# sensorboard.net
KiCad netlist of a schematic drawn in EAGLE
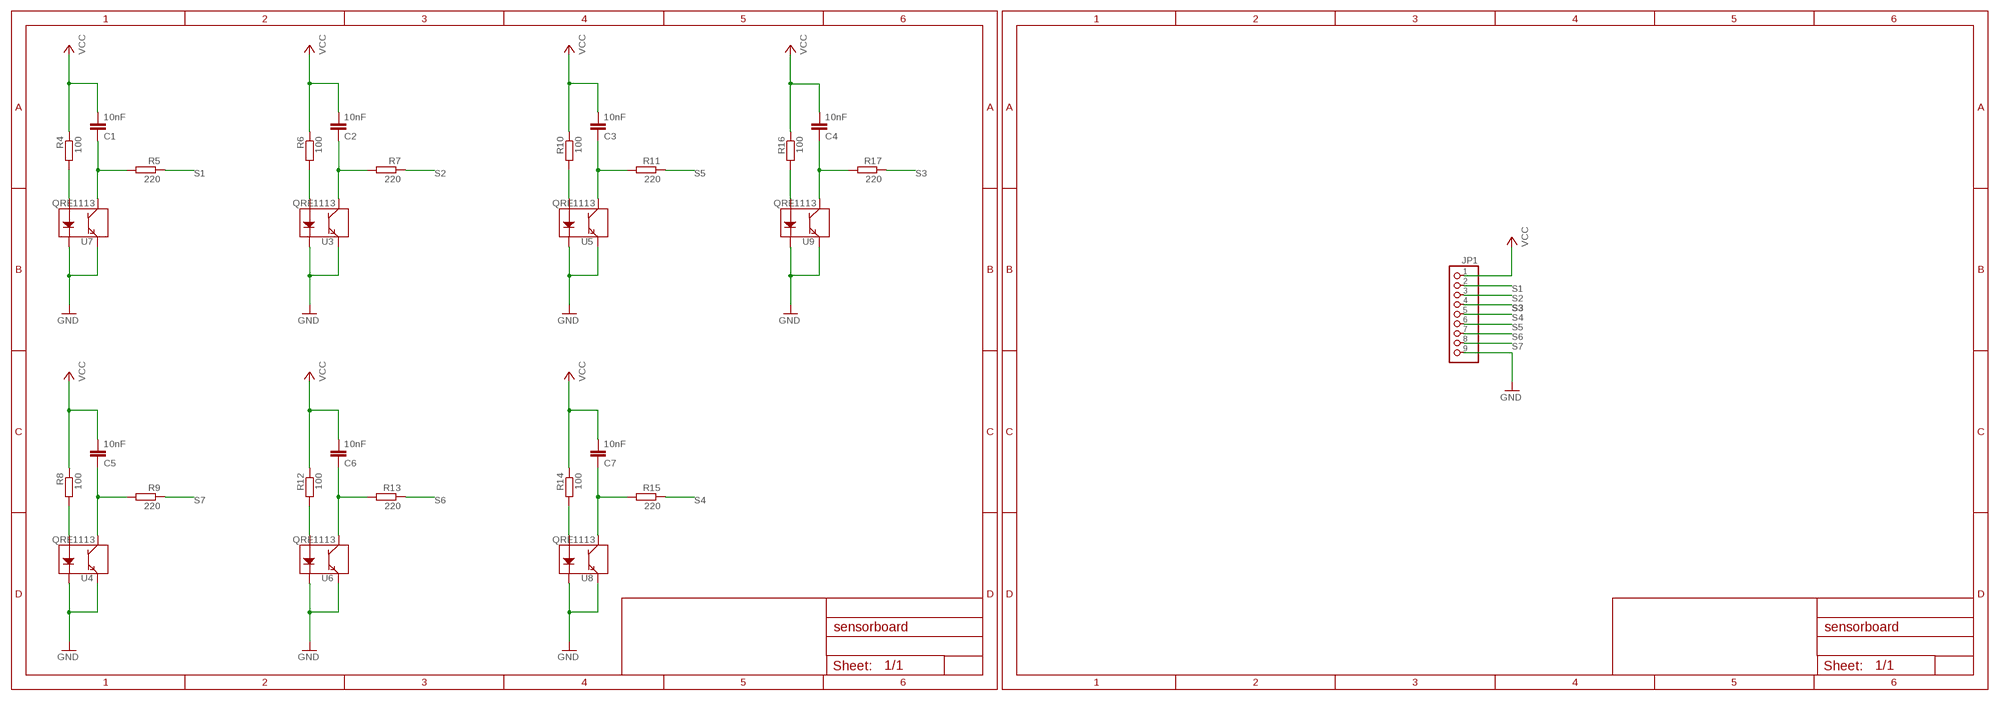
[diagram p0: schematic, sheet 1]

(export (version "E")
  (design (tool "Eeschema 10.0.6"))
  (components
    (comp (ref "C1")
      (value "10nF")
      (footprint "eagle-import:C0805K")
      (libsource (lib "eagle-import") (part "C-EUC0805K"))
    )
    (comp (ref "C2")
      (value "10nF")
      (footprint "eagle-import:C0805K")
      (libsource (lib "eagle-import") (part "C-EUC0805K"))
    )
    (comp (ref "C3")
      (value "10nF")
      (footprint "eagle-import:C0805K")
      (libsource (lib "eagle-import") (part "C-EUC0805K"))
    )
    (comp (ref "C4")
      (value "10nF")
      (footprint "eagle-import:C0805K")
      (libsource (lib "eagle-import") (part "C-EUC0805K"))
    )
    (comp (ref "C5")
      (value "10nF")
      (footprint "eagle-import:C0805K")
      (libsource (lib "eagle-import") (part "C-EUC0805K"))
    )
    (comp (ref "C6")
      (value "10nF")
      (footprint "eagle-import:C0805K")
      (libsource (lib "eagle-import") (part "C-EUC0805K"))
    )
    (comp (ref "C7")
      (value "10nF")
      (footprint "eagle-import:C0805K")
      (libsource (lib "eagle-import") (part "C-EUC0805K"))
    )
    (comp (ref "JP1")
      (value "PINHD-1X9")
      (footprint "eagle-import:1X09")
      (libsource (lib "eagle-import") (part "PINHD-1X9"))
    )
    (comp (ref "R4")
      (value "100")
      (footprint "eagle-import:M0805")
      (libsource (lib "eagle-import") (part "R-EU_M0805"))
    )
    (comp (ref "R5")
      (value "220")
      (footprint "eagle-import:M0805")
      (libsource (lib "eagle-import") (part "R-EU_M0805"))
    )
    (comp (ref "R6")
      (value "100")
      (footprint "eagle-import:M0805")
      (libsource (lib "eagle-import") (part "R-EU_M0805"))
    )
    (comp (ref "R7")
      (value "220")
      (footprint "eagle-import:M0805")
      (libsource (lib "eagle-import") (part "R-EU_M0805"))
    )
    (comp (ref "R8")
      (value "100")
      (footprint "eagle-import:M0805")
      (libsource (lib "eagle-import") (part "R-EU_M0805"))
    )
    (comp (ref "R9")
      (value "220")
      (footprint "eagle-import:M0805")
      (libsource (lib "eagle-import") (part "R-EU_M0805"))
    )
    (comp (ref "R10")
      (value "100")
      (footprint "eagle-import:M0805")
      (libsource (lib "eagle-import") (part "R-EU_M0805"))
    )
    (comp (ref "R11")
      (value "220")
      (footprint "eagle-import:M0805")
      (libsource (lib "eagle-import") (part "R-EU_M0805"))
    )
    (comp (ref "R12")
      (value "100")
      (footprint "eagle-import:M0805")
      (libsource (lib "eagle-import") (part "R-EU_M0805"))
    )
    (comp (ref "R13")
      (value "220")
      (footprint "eagle-import:M0805")
      (libsource (lib "eagle-import") (part "R-EU_M0805"))
    )
    (comp (ref "R14")
      (value "100")
      (footprint "eagle-import:M0805")
      (libsource (lib "eagle-import") (part "R-EU_M0805"))
    )
    (comp (ref "R15")
      (value "220")
      (footprint "eagle-import:M0805")
      (libsource (lib "eagle-import") (part "R-EU_M0805"))
    )
    (comp (ref "R16")
      (value "100")
      (footprint "eagle-import:M0805")
      (libsource (lib "eagle-import") (part "R-EU_M0805"))
    )
    (comp (ref "R17")
      (value "220")
      (footprint "eagle-import:M0805")
      (libsource (lib "eagle-import") (part "R-EU_M0805"))
    )
    (comp (ref "U3")
      (value "QRE1113")
      (footprint "eagle-import:QRE1113")
      (libsource (lib "eagle-import") (part "QRE1113"))
    )
    (comp (ref "U4")
      (value "QRE1113")
      (footprint "eagle-import:QRE1113")
      (libsource (lib "eagle-import") (part "QRE1113"))
    )
    (comp (ref "U5")
      (value "QRE1113")
      (footprint "eagle-import:QRE1113")
      (libsource (lib "eagle-import") (part "QRE1113"))
    )
    (comp (ref "U6")
      (value "QRE1113")
      (footprint "eagle-import:QRE1113")
      (libsource (lib "eagle-import") (part "QRE1113"))
    )
    (comp (ref "U7")
      (value "QRE1113")
      (footprint "eagle-import:QRE1113")
      (libsource (lib "eagle-import") (part "QRE1113"))
    )
    (comp (ref "U8")
      (value "QRE1113")
      (footprint "eagle-import:QRE1113")
      (libsource (lib "eagle-import") (part "QRE1113"))
    )
    (comp (ref "U9")
      (value "QRE1113")
      (footprint "eagle-import:QRE1113")
      (libsource (lib "eagle-import") (part "QRE1113"))
    )
  )
  (nets
    (net (code "1") (name "/S1") (class "Default")
      (node (ref "JP1") (pin "2") (pinfunction "2_2") (pintype "passive"))
      (node (ref "R5") (pin "1") (pinfunction "1_1") (pintype "passive"))
    )
    (net (code "2") (name "/S2") (class "Default")
      (node (ref "JP1") (pin "3") (pinfunction "3_3") (pintype "passive"))
      (node (ref "R7") (pin "1") (pinfunction "1_1") (pintype "passive"))
    )
    (net (code "3") (name "/S3") (class "Default")
      (node (ref "JP1") (pin "4") (pinfunction "4_4") (pintype "passive"))
      (node (ref "R17") (pin "1") (pinfunction "1_1") (pintype "passive"))
    )
    (net (code "4") (name "/S4") (class "Default")
      (node (ref "JP1") (pin "5") (pinfunction "5_5") (pintype "passive"))
      (node (ref "R15") (pin "1") (pinfunction "1_1") (pintype "passive"))
    )
    (net (code "5") (name "/S5") (class "Default")
      (node (ref "JP1") (pin "6") (pinfunction "6_6") (pintype "passive"))
      (node (ref "R11") (pin "1") (pinfunction "1_1") (pintype "passive"))
    )
    (net (code "6") (name "/S6") (class "Default")
      (node (ref "JP1") (pin "7") (pinfunction "7_7") (pintype "passive"))
      (node (ref "R13") (pin "1") (pinfunction "1_1") (pintype "passive"))
    )
    (net (code "7") (name "/S7") (class "Default")
      (node (ref "JP1") (pin "8") (pinfunction "8_8") (pintype "passive"))
      (node (ref "R9") (pin "1") (pinfunction "1_1") (pintype "passive"))
    )
    (net (code "8") (name "GND") (class "Default")
      (node (ref "JP1") (pin "9") (pinfunction "9_9") (pintype "passive"))
      (node (ref "U3") (pin "2") (pinfunction "K_2") (pintype "bidirectional"))
      (node (ref "U3") (pin "4") (pinfunction "E_4") (pintype "bidirectional"))
      (node (ref "U4") (pin "2") (pinfunction "K_2") (pintype "bidirectional"))
      (node (ref "U4") (pin "4") (pinfunction "E_4") (pintype "bidirectional"))
      (node (ref "U5") (pin "2") (pinfunction "K_2") (pintype "bidirectional"))
      (node (ref "U5") (pin "4") (pinfunction "E_4") (pintype "bidirectional"))
      (node (ref "U6") (pin "2") (pinfunction "K_2") (pintype "bidirectional"))
      (node (ref "U6") (pin "4") (pinfunction "E_4") (pintype "bidirectional"))
      (node (ref "U7") (pin "2") (pinfunction "K_2") (pintype "bidirectional"))
      (node (ref "U7") (pin "4") (pinfunction "E_4") (pintype "bidirectional"))
      (node (ref "U8") (pin "2") (pinfunction "K_2") (pintype "bidirectional"))
      (node (ref "U8") (pin "4") (pinfunction "E_4") (pintype "bidirectional"))
      (node (ref "U9") (pin "2") (pinfunction "K_2") (pintype "bidirectional"))
      (node (ref "U9") (pin "4") (pinfunction "E_4") (pintype "bidirectional"))
    )
    (net (code "9") (name "Net-(U3-A)") (class "Default")
      (node (ref "R6") (pin "2") (pinfunction "2_2") (pintype "passive"))
      (node (ref "U3") (pin "1") (pinfunction "A_1") (pintype "bidirectional"))
    )
    (net (code "10") (name "Net-(U3-C)") (class "Default")
      (node (ref "C2") (pin "1") (pinfunction "1_1") (pintype "passive"))
      (node (ref "R7") (pin "2") (pinfunction "2_2") (pintype "passive"))
      (node (ref "U3") (pin "3") (pinfunction "C_3") (pintype "bidirectional"))
    )
    (net (code "11") (name "Net-(U4-A)") (class "Default")
      (node (ref "R8") (pin "2") (pinfunction "2_2") (pintype "passive"))
      (node (ref "U4") (pin "1") (pinfunction "A_1") (pintype "bidirectional"))
    )
    (net (code "12") (name "Net-(U4-C)") (class "Default")
      (node (ref "C5") (pin "1") (pinfunction "1_1") (pintype "passive"))
      (node (ref "R9") (pin "2") (pinfunction "2_2") (pintype "passive"))
      (node (ref "U4") (pin "3") (pinfunction "C_3") (pintype "bidirectional"))
    )
    (net (code "13") (name "Net-(U5-A)") (class "Default")
      (node (ref "R10") (pin "2") (pinfunction "2_2") (pintype "passive"))
      (node (ref "U5") (pin "1") (pinfunction "A_1") (pintype "bidirectional"))
    )
    (net (code "14") (name "Net-(U5-C)") (class "Default")
      (node (ref "C3") (pin "1") (pinfunction "1_1") (pintype "passive"))
      (node (ref "R11") (pin "2") (pinfunction "2_2") (pintype "passive"))
      (node (ref "U5") (pin "3") (pinfunction "C_3") (pintype "bidirectional"))
    )
    (net (code "15") (name "Net-(U6-A)") (class "Default")
      (node (ref "R12") (pin "2") (pinfunction "2_2") (pintype "passive"))
      (node (ref "U6") (pin "1") (pinfunction "A_1") (pintype "bidirectional"))
    )
    (net (code "16") (name "Net-(U6-C)") (class "Default")
      (node (ref "C6") (pin "1") (pinfunction "1_1") (pintype "passive"))
      (node (ref "R13") (pin "2") (pinfunction "2_2") (pintype "passive"))
      (node (ref "U6") (pin "3") (pinfunction "C_3") (pintype "bidirectional"))
    )
    (net (code "17") (name "Net-(U7-A)") (class "Default")
      (node (ref "R4") (pin "2") (pinfunction "2_2") (pintype "passive"))
      (node (ref "U7") (pin "1") (pinfunction "A_1") (pintype "bidirectional"))
    )
    (net (code "18") (name "Net-(U7-C)") (class "Default")
      (node (ref "C1") (pin "1") (pinfunction "1_1") (pintype "passive"))
      (node (ref "R5") (pin "2") (pinfunction "2_2") (pintype "passive"))
      (node (ref "U7") (pin "3") (pinfunction "C_3") (pintype "bidirectional"))
    )
    (net (code "19") (name "Net-(U8-A)") (class "Default")
      (node (ref "R14") (pin "2") (pinfunction "2_2") (pintype "passive"))
      (node (ref "U8") (pin "1") (pinfunction "A_1") (pintype "bidirectional"))
    )
    (net (code "20") (name "Net-(U8-C)") (class "Default")
      (node (ref "C7") (pin "1") (pinfunction "1_1") (pintype "passive"))
      (node (ref "R15") (pin "2") (pinfunction "2_2") (pintype "passive"))
      (node (ref "U8") (pin "3") (pinfunction "C_3") (pintype "bidirectional"))
    )
    (net (code "21") (name "Net-(U9-A)") (class "Default")
      (node (ref "R16") (pin "2") (pinfunction "2_2") (pintype "passive"))
      (node (ref "U9") (pin "1") (pinfunction "A_1") (pintype "bidirectional"))
    )
    (net (code "22") (name "Net-(U9-C)") (class "Default")
      (node (ref "C4") (pin "1") (pinfunction "1_1") (pintype "passive"))
      (node (ref "R17") (pin "2") (pinfunction "2_2") (pintype "passive"))
      (node (ref "U9") (pin "3") (pinfunction "C_3") (pintype "bidirectional"))
    )
    (net (code "23") (name "VCC") (class "Default")
      (node (ref "C1") (pin "2") (pinfunction "2_2") (pintype "passive"))
      (node (ref "C2") (pin "2") (pinfunction "2_2") (pintype "passive"))
      (node (ref "C3") (pin "2") (pinfunction "2_2") (pintype "passive"))
      (node (ref "C4") (pin "2") (pinfunction "2_2") (pintype "passive"))
      (node (ref "C5") (pin "2") (pinfunction "2_2") (pintype "passive"))
      (node (ref "C6") (pin "2") (pinfunction "2_2") (pintype "passive"))
      (node (ref "C7") (pin "2") (pinfunction "2_2") (pintype "passive"))
      (node (ref "JP1") (pin "1") (pinfunction "1_1") (pintype "passive"))
      (node (ref "R10") (pin "1") (pinfunction "1_1") (pintype "passive"))
      (node (ref "R12") (pin "1") (pinfunction "1_1") (pintype "passive"))
      (node (ref "R14") (pin "1") (pinfunction "1_1") (pintype "passive"))
      (node (ref "R16") (pin "1") (pinfunction "1_1") (pintype "passive"))
      (node (ref "R4") (pin "1") (pinfunction "1_1") (pintype "passive"))
      (node (ref "R6") (pin "1") (pinfunction "1_1") (pintype "passive"))
      (node (ref "R8") (pin "1") (pinfunction "1_1") (pintype "passive"))
    )
  )
)
